# pcb.net
KiCad netlist of a schematic drawn in Altium Designer
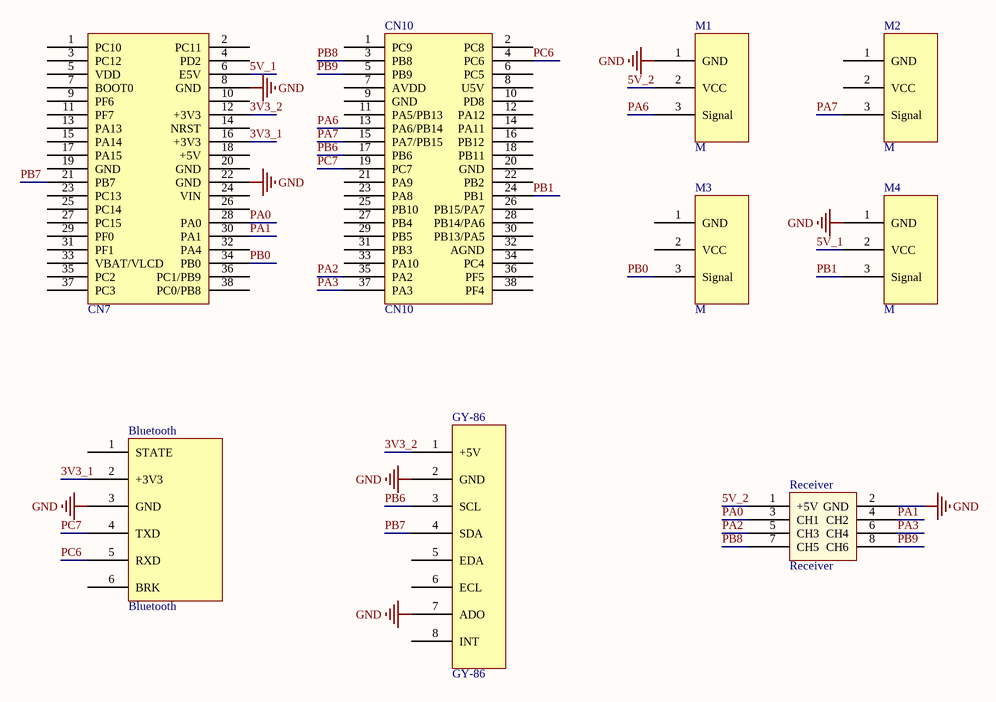
[diagram p0: pcb.SchDoc]

(export (version "E")
  (design (tool "Eeschema 10.0.6"))
  (components
    (comp (ref "Bluetooth")
      (value "Bluetooth")
      (footprint "Bluetooth")
      (libsource (lib "Integrated_Library") (part "Bluetooth"))
    )
    (comp (ref "CN7") (value "CN7") (footprint "CN7") (libsource (lib "Integrated_Library") (part "CN7")))
    (comp (ref "CN10") (value "CN10") (footprint "CN10") (libsource (lib "Integrated_Library") (part "CN10")))
    (comp (ref "GY-86")
      (value "GY-86")
      (footprint "GY-86")
      (libsource (lib "Integrated_Library") (part "GY-86"))
    )
    (comp (ref "M1") (value "M") (footprint "M") (libsource (lib "Integrated_Library") (part "M")))
    (comp (ref "M2") (value "M") (footprint "M") (libsource (lib "Integrated_Library") (part "M")))
    (comp (ref "M3") (value "M") (footprint "M") (libsource (lib "Integrated_Library") (part "M")))
    (comp (ref "M4") (value "M") (footprint "M") (libsource (lib "Integrated_Library") (part "M")))
    (comp (ref "Receiver")
      (value "Receiver")
      (footprint "Receiver")
      (libsource (lib "Integrated_Library") (part "Receiver"))
    )
  )
  (nets
    (net (code "1") (name "/3V3_1") (class "Default")
      (node (ref "Bluetooth") (pin "2") (pinfunction "+3V3_2") (pintype "passive"))
      (node (ref "CN7") (pin "16") (pinfunction "+3V3_16") (pintype "passive"))
    )
    (net (code "2") (name "/3V3_2") (class "Default")
      (node (ref "CN7") (pin "12") (pinfunction "+3V3_12") (pintype "passive"))
      (node (ref "GY-86") (pin "1") (pinfunction "+5V_1") (pintype "passive"))
    )
    (net (code "3") (name "/5V_1") (class "Default")
      (node (ref "CN7") (pin "6") (pinfunction "E5V_6") (pintype "passive"))
      (node (ref "M4") (pin "2") (pinfunction "VCC_2") (pintype "passive"))
    )
    (net (code "4") (name "/5V_2") (class "Default")
      (node (ref "M1") (pin "2") (pinfunction "VCC_2") (pintype "passive"))
      (node (ref "Receiver") (pin "1") (pinfunction "+5V_1") (pintype "passive"))
    )
    (net (code "6") (name "/PA0") (class "Default")
      (node (ref "CN7") (pin "28") (pinfunction "PA0_28") (pintype "passive"))
      (node (ref "Receiver") (pin "3") (pinfunction "CH1_3") (pintype "passive"))
    )
    (net (code "7") (name "/PA1") (class "Default")
      (node (ref "CN7") (pin "30") (pinfunction "PA1_30") (pintype "passive"))
      (node (ref "Receiver") (pin "4") (pinfunction "CH2_4") (pintype "passive"))
    )
    (net (code "8") (name "/PA2") (class "Default")
      (node (ref "CN10") (pin "35") (pinfunction "PA2_35") (pintype "passive"))
      (node (ref "Receiver") (pin "5") (pinfunction "CH3_5") (pintype "passive"))
    )
    (net (code "9") (name "/PA3") (class "Default")
      (node (ref "CN10") (pin "37") (pinfunction "PA3_37") (pintype "passive"))
      (node (ref "Receiver") (pin "6") (pinfunction "CH4_6") (pintype "passive"))
    )
    (net (code "10") (name "/PA6") (class "Default")
      (node (ref "CN10") (pin "13") (pinfunction "PA6/PB14_13") (pintype "passive"))
      (node (ref "M1") (pin "3") (pinfunction "Signal_3") (pintype "passive"))
    )
    (net (code "11") (name "/PA7") (class "Default")
      (node (ref "CN10") (pin "15") (pinfunction "PA7/PB15_15") (pintype "passive"))
      (node (ref "M2") (pin "3") (pinfunction "Signal_3") (pintype "passive"))
    )
    (net (code "12") (name "/PB0") (class "Default")
      (node (ref "CN7") (pin "34") (pinfunction "PB0_34") (pintype "passive"))
      (node (ref "M3") (pin "3") (pinfunction "Signal_3") (pintype "passive"))
    )
    (net (code "13") (name "/PB1") (class "Default")
      (node (ref "CN10") (pin "24") (pinfunction "PB1_24") (pintype "passive"))
      (node (ref "M4") (pin "3") (pinfunction "Signal_3") (pintype "passive"))
    )
    (net (code "14") (name "/PB6") (class "Default")
      (node (ref "CN10") (pin "17") (pinfunction "PB6_17") (pintype "passive"))
      (node (ref "GY-86") (pin "3") (pinfunction "SCL_3") (pintype "passive"))
    )
    (net (code "15") (name "/PB7") (class "Default")
      (node (ref "CN7") (pin "21") (pinfunction "PB7_21") (pintype "passive"))
      (node (ref "GY-86") (pin "4") (pinfunction "SDA_4") (pintype "passive"))
    )
    (net (code "16") (name "/PB8") (class "Default")
      (node (ref "CN10") (pin "3") (pinfunction "PB8_3") (pintype "passive"))
      (node (ref "Receiver") (pin "7") (pinfunction "CH5_7") (pintype "passive"))
    )
    (net (code "17") (name "/PB9") (class "Default")
      (node (ref "CN10") (pin "5") (pinfunction "PB9_5") (pintype "passive"))
      (node (ref "Receiver") (pin "8") (pinfunction "CH6_8") (pintype "passive"))
    )
    (net (code "18") (name "/PC6") (class "Default")
      (node (ref "Bluetooth") (pin "5") (pinfunction "RXD_5") (pintype "passive"))
      (node (ref "CN10") (pin "4") (pinfunction "PC6_4") (pintype "passive"))
    )
    (net (code "19") (name "/PC7") (class "Default")
      (node (ref "Bluetooth") (pin "4") (pinfunction "TXD_4") (pintype "passive"))
      (node (ref "CN10") (pin "19") (pinfunction "PC7_19") (pintype "passive"))
    )
    (net (code "20") (name "GND") (class "Default")
      (node (ref "Bluetooth") (pin "3") (pinfunction "GND_3") (pintype "passive"))
      (node (ref "CN7") (pin "22") (pinfunction "GND_22") (pintype "passive"))
      (node (ref "CN7") (pin "8") (pinfunction "GND_8") (pintype "passive"))
      (node (ref "GY-86") (pin "2") (pinfunction "GND_2") (pintype "passive"))
      (node (ref "GY-86") (pin "7") (pinfunction "ADO_7") (pintype "passive"))
      (node (ref "M1") (pin "1") (pinfunction "GND_1") (pintype "passive"))
      (node (ref "M4") (pin "1") (pinfunction "GND_1") (pintype "passive"))
      (node (ref "Receiver") (pin "2") (pinfunction "GND_2") (pintype "passive"))
    )
    (net (code "21") (name "unconnected-(Bluetooth-BRK-Pad6)") (class "Default")
      (node (ref "Bluetooth") (pin "6") (pinfunction "BRK_6") (pintype "passive"))
    )
    (net (code "22") (name "unconnected-(Bluetooth-STATE-Pad1)") (class "Default")
      (node (ref "Bluetooth") (pin "1") (pinfunction "STATE_1") (pintype "passive"))
    )
    (net (code "23") (name "unconnected-(CN7-+5V-Pad18)") (class "Default")
      (node (ref "CN7") (pin "18") (pinfunction "+5V_18") (pintype "passive"))
    )
    (net (code "24") (name "unconnected-(CN7-BOOT0-Pad7)") (class "Default")
      (node (ref "CN7") (pin "7") (pinfunction "BOOT0_7") (pintype "passive"))
    )
    (net (code "25") (name "unconnected-(CN7-GND-Pad19)") (class "Default")
      (node (ref "CN7") (pin "19") (pinfunction "GND_19") (pintype "passive"))
    )
    (net (code "26") (name "unconnected-(CN7-GND-Pad20)") (class "Default")
      (node (ref "CN7") (pin "20") (pinfunction "GND_20") (pintype "passive"))
    )
    (net (code "27") (name "unconnected-(CN7-NRST-Pad14)") (class "Default")
      (node (ref "CN7") (pin "14") (pinfunction "NRST_14") (pintype "passive"))
    )
    (net (code "28") (name "unconnected-(CN7-PA4-Pad32)") (class "Default")
      (node (ref "CN7") (pin "32") (pinfunction "PA4_32") (pintype "passive"))
    )
    (net (code "29") (name "unconnected-(CN7-PA13-Pad13)") (class "Default")
      (node (ref "CN7") (pin "13") (pinfunction "PA13_13") (pintype "passive"))
    )
    (net (code "30") (name "unconnected-(CN7-PA14-Pad15)") (class "Default")
      (node (ref "CN7") (pin "15") (pinfunction "PA14_15") (pintype "passive"))
    )
    (net (code "31") (name "unconnected-(CN7-PA15-Pad17)") (class "Default")
      (node (ref "CN7") (pin "17") (pinfunction "PA15_17") (pintype "passive"))
    )
    (net (code "32") (name "unconnected-(CN7-PC0{slash}PB8-Pad38)") (class "Default")
      (node (ref "CN7") (pin "38") (pinfunction "PC0/PB8_38") (pintype "passive"))
    )
    (net (code "33") (name "unconnected-(CN7-PC1{slash}PB9-Pad36)") (class "Default")
      (node (ref "CN7") (pin "36") (pinfunction "PC1/PB9_36") (pintype "passive"))
    )
    (net (code "34") (name "unconnected-(CN7-PC2-Pad35)") (class "Default")
      (node (ref "CN7") (pin "35") (pinfunction "PC2_35") (pintype "passive"))
    )
    (net (code "35") (name "unconnected-(CN7-PC3-Pad37)") (class "Default")
      (node (ref "CN7") (pin "37") (pinfunction "PC3_37") (pintype "passive"))
    )
    (net (code "36") (name "unconnected-(CN7-PC10-Pad1)") (class "Default")
      (node (ref "CN7") (pin "1") (pinfunction "PC10_1") (pintype "passive"))
    )
    (net (code "37") (name "unconnected-(CN7-PC11-Pad2)") (class "Default")
      (node (ref "CN7") (pin "2") (pinfunction "PC11_2") (pintype "passive"))
    )
    (net (code "38") (name "unconnected-(CN7-PC12-Pad3)") (class "Default")
      (node (ref "CN7") (pin "3") (pinfunction "PC12_3") (pintype "passive"))
    )
    (net (code "39") (name "unconnected-(CN7-PC13-Pad23)") (class "Default")
      (node (ref "CN7") (pin "23") (pinfunction "PC13_23") (pintype "passive"))
    )
    (net (code "40") (name "unconnected-(CN7-PC14-Pad25)") (class "Default")
      (node (ref "CN7") (pin "25") (pinfunction "PC14_25") (pintype "passive"))
    )
    (net (code "41") (name "unconnected-(CN7-PC15-Pad27)") (class "Default")
      (node (ref "CN7") (pin "27") (pinfunction "PC15_27") (pintype "passive"))
    )
    (net (code "42") (name "unconnected-(CN7-PD2-Pad4)") (class "Default")
      (node (ref "CN7") (pin "4") (pinfunction "PD2_4") (pintype "passive"))
    )
    (net (code "43") (name "unconnected-(CN7-PF0-Pad29)") (class "Default")
      (node (ref "CN7") (pin "29") (pinfunction "PF0_29") (pintype "passive"))
    )
    (net (code "44") (name "unconnected-(CN7-PF1-Pad31)") (class "Default")
      (node (ref "CN7") (pin "31") (pinfunction "PF1_31") (pintype "passive"))
    )
    (net (code "45") (name "unconnected-(CN7-PF6-Pad9)") (class "Default")
      (node (ref "CN7") (pin "9") (pinfunction "PF6_9") (pintype "passive"))
    )
    (net (code "46") (name "unconnected-(CN7-PF7-Pad11)") (class "Default")
      (node (ref "CN7") (pin "11") (pinfunction "PF7_11") (pintype "passive"))
    )
    (net (code "47") (name "unconnected-(CN7-Pad10)") (class "Default")
      (node (ref "CN7") (pin "10") (pintype "passive"))
    )
    (net (code "48") (name "unconnected-(CN7-Pad26)") (class "Default")
      (node (ref "CN7") (pin "26") (pintype "passive"))
    )
    (net (code "49") (name "unconnected-(CN7-VBAT{slash}VLCD-Pad33)") (class "Default")
      (node (ref "CN7") (pin "33") (pinfunction "VBAT/VLCD_33") (pintype "passive"))
    )
    (net (code "50") (name "unconnected-(CN7-VDD-Pad5)") (class "Default")
      (node (ref "CN7") (pin "5") (pinfunction "VDD_5") (pintype "passive"))
    )
    (net (code "51") (name "unconnected-(CN7-VIN-Pad24)") (class "Default")
      (node (ref "CN7") (pin "24") (pinfunction "VIN_24") (pintype "passive"))
    )
    (net (code "52") (name "unconnected-(CN10-AGND-Pad32)") (class "Default")
      (node (ref "CN10") (pin "32") (pinfunction "AGND_32") (pintype "passive"))
    )
    (net (code "53") (name "unconnected-(CN10-AVDD-Pad7)") (class "Default")
      (node (ref "CN10") (pin "7") (pinfunction "AVDD_7") (pintype "passive"))
    )
    (net (code "54") (name "unconnected-(CN10-GND-Pad9)") (class "Default")
      (node (ref "CN10") (pin "9") (pinfunction "GND_9") (pintype "passive"))
    )
    (net (code "55") (name "unconnected-(CN10-GND-Pad20)") (class "Default")
      (node (ref "CN10") (pin "20") (pinfunction "GND_20") (pintype "passive"))
    )
    (net (code "56") (name "unconnected-(CN10-PA5{slash}PB13-Pad11)") (class "Default")
      (node (ref "CN10") (pin "11") (pinfunction "PA5/PB13_11") (pintype "passive"))
    )
    (net (code "57") (name "unconnected-(CN10-PA8-Pad23)") (class "Default")
      (node (ref "CN10") (pin "23") (pinfunction "PA8_23") (pintype "passive"))
    )
    (net (code "58") (name "unconnected-(CN10-PA9-Pad21)") (class "Default")
      (node (ref "CN10") (pin "21") (pinfunction "PA9_21") (pintype "passive"))
    )
    (net (code "59") (name "unconnected-(CN10-PA10-Pad33)") (class "Default")
      (node (ref "CN10") (pin "33") (pinfunction "PA10_33") (pintype "passive"))
    )
    (net (code "60") (name "unconnected-(CN10-PA11-Pad14)") (class "Default")
      (node (ref "CN10") (pin "14") (pinfunction "PA11_14") (pintype "passive"))
    )
    (net (code "61") (name "unconnected-(CN10-PA12-Pad12)") (class "Default")
      (node (ref "CN10") (pin "12") (pinfunction "PA12_12") (pintype "passive"))
    )
    (net (code "62") (name "unconnected-(CN10-PB2-Pad22)") (class "Default")
      (node (ref "CN10") (pin "22") (pinfunction "PB2_22") (pintype "passive"))
    )
    (net (code "63") (name "unconnected-(CN10-PB3-Pad31)") (class "Default")
      (node (ref "CN10") (pin "31") (pinfunction "PB3_31") (pintype "passive"))
    )
    (net (code "64") (name "unconnected-(CN10-PB4-Pad27)") (class "Default")
      (node (ref "CN10") (pin "27") (pinfunction "PB4_27") (pintype "passive"))
    )
    (net (code "65") (name "unconnected-(CN10-PB5-Pad29)") (class "Default")
      (node (ref "CN10") (pin "29") (pinfunction "PB5_29") (pintype "passive"))
    )
    (net (code "66") (name "unconnected-(CN10-PB10-Pad25)") (class "Default")
      (node (ref "CN10") (pin "25") (pinfunction "PB10_25") (pintype "passive"))
    )
    (net (code "67") (name "unconnected-(CN10-PB11-Pad18)") (class "Default")
      (node (ref "CN10") (pin "18") (pinfunction "PB11_18") (pintype "passive"))
    )
    (net (code "68") (name "unconnected-(CN10-PB12-Pad16)") (class "Default")
      (node (ref "CN10") (pin "16") (pinfunction "PB12_16") (pintype "passive"))
    )
    (net (code "69") (name "unconnected-(CN10-PB13{slash}PA5-Pad30)") (class "Default")
      (node (ref "CN10") (pin "30") (pinfunction "PB13/PA5_30") (pintype "passive"))
    )
    (net (code "70") (name "unconnected-(CN10-PB14{slash}PA6-Pad28)") (class "Default")
      (node (ref "CN10") (pin "28") (pinfunction "PB14/PA6_28") (pintype "passive"))
    )
    (net (code "71") (name "unconnected-(CN10-PB15{slash}PA7-Pad26)") (class "Default")
      (node (ref "CN10") (pin "26") (pinfunction "PB15/PA7_26") (pintype "passive"))
    )
    (net (code "72") (name "unconnected-(CN10-PC4-Pad34)") (class "Default")
      (node (ref "CN10") (pin "34") (pinfunction "PC4_34") (pintype "passive"))
    )
    (net (code "73") (name "unconnected-(CN10-PC5-Pad6)") (class "Default")
      (node (ref "CN10") (pin "6") (pinfunction "PC5_6") (pintype "passive"))
    )
    (net (code "74") (name "unconnected-(CN10-PC8-Pad2)") (class "Default")
      (node (ref "CN10") (pin "2") (pinfunction "PC8_2") (pintype "passive"))
    )
    (net (code "75") (name "unconnected-(CN10-PC9-Pad1)") (class "Default")
      (node (ref "CN10") (pin "1") (pinfunction "PC9_1") (pintype "passive"))
    )
    (net (code "76") (name "unconnected-(CN10-PD8-Pad10)") (class "Default")
      (node (ref "CN10") (pin "10") (pinfunction "PD8_10") (pintype "passive"))
    )
    (net (code "77") (name "unconnected-(CN10-PF4-Pad38)") (class "Default")
      (node (ref "CN10") (pin "38") (pinfunction "PF4_38") (pintype "passive"))
    )
    (net (code "78") (name "unconnected-(CN10-PF5-Pad36)") (class "Default")
      (node (ref "CN10") (pin "36") (pinfunction "PF5_36") (pintype "passive"))
    )
    (net (code "79") (name "unconnected-(CN10-U5V-Pad8)") (class "Default")
      (node (ref "CN10") (pin "8") (pinfunction "U5V_8") (pintype "passive"))
    )
    (net (code "80") (name "unconnected-(GY-86-ECL-Pad6)") (class "Default")
      (node (ref "GY-86") (pin "6") (pinfunction "ECL_6") (pintype "passive"))
    )
    (net (code "81") (name "unconnected-(GY-86-EDA-Pad5)") (class "Default")
      (node (ref "GY-86") (pin "5") (pinfunction "EDA_5") (pintype "passive"))
    )
    (net (code "82") (name "unconnected-(GY-86-INT-Pad8)") (class "Default")
      (node (ref "GY-86") (pin "8") (pinfunction "INT_8") (pintype "passive"))
    )
    (net (code "83") (name "unconnected-(M2-GND-Pad1)") (class "Default")
      (node (ref "M2") (pin "1") (pinfunction "GND_1") (pintype "passive"))
    )
    (net (code "84") (name "unconnected-(M2-VCC-Pad2)") (class "Default")
      (node (ref "M2") (pin "2") (pinfunction "VCC_2") (pintype "passive"))
    )
    (net (code "85") (name "unconnected-(M3-GND-Pad1)") (class "Default")
      (node (ref "M3") (pin "1") (pinfunction "GND_1") (pintype "passive"))
    )
    (net (code "86") (name "unconnected-(M3-VCC-Pad2)") (class "Default")
      (node (ref "M3") (pin "2") (pinfunction "VCC_2") (pintype "passive"))
    )
  )
)
